# adrone_v1.net
KiCad netlist of a schematic drawn in EAGLE
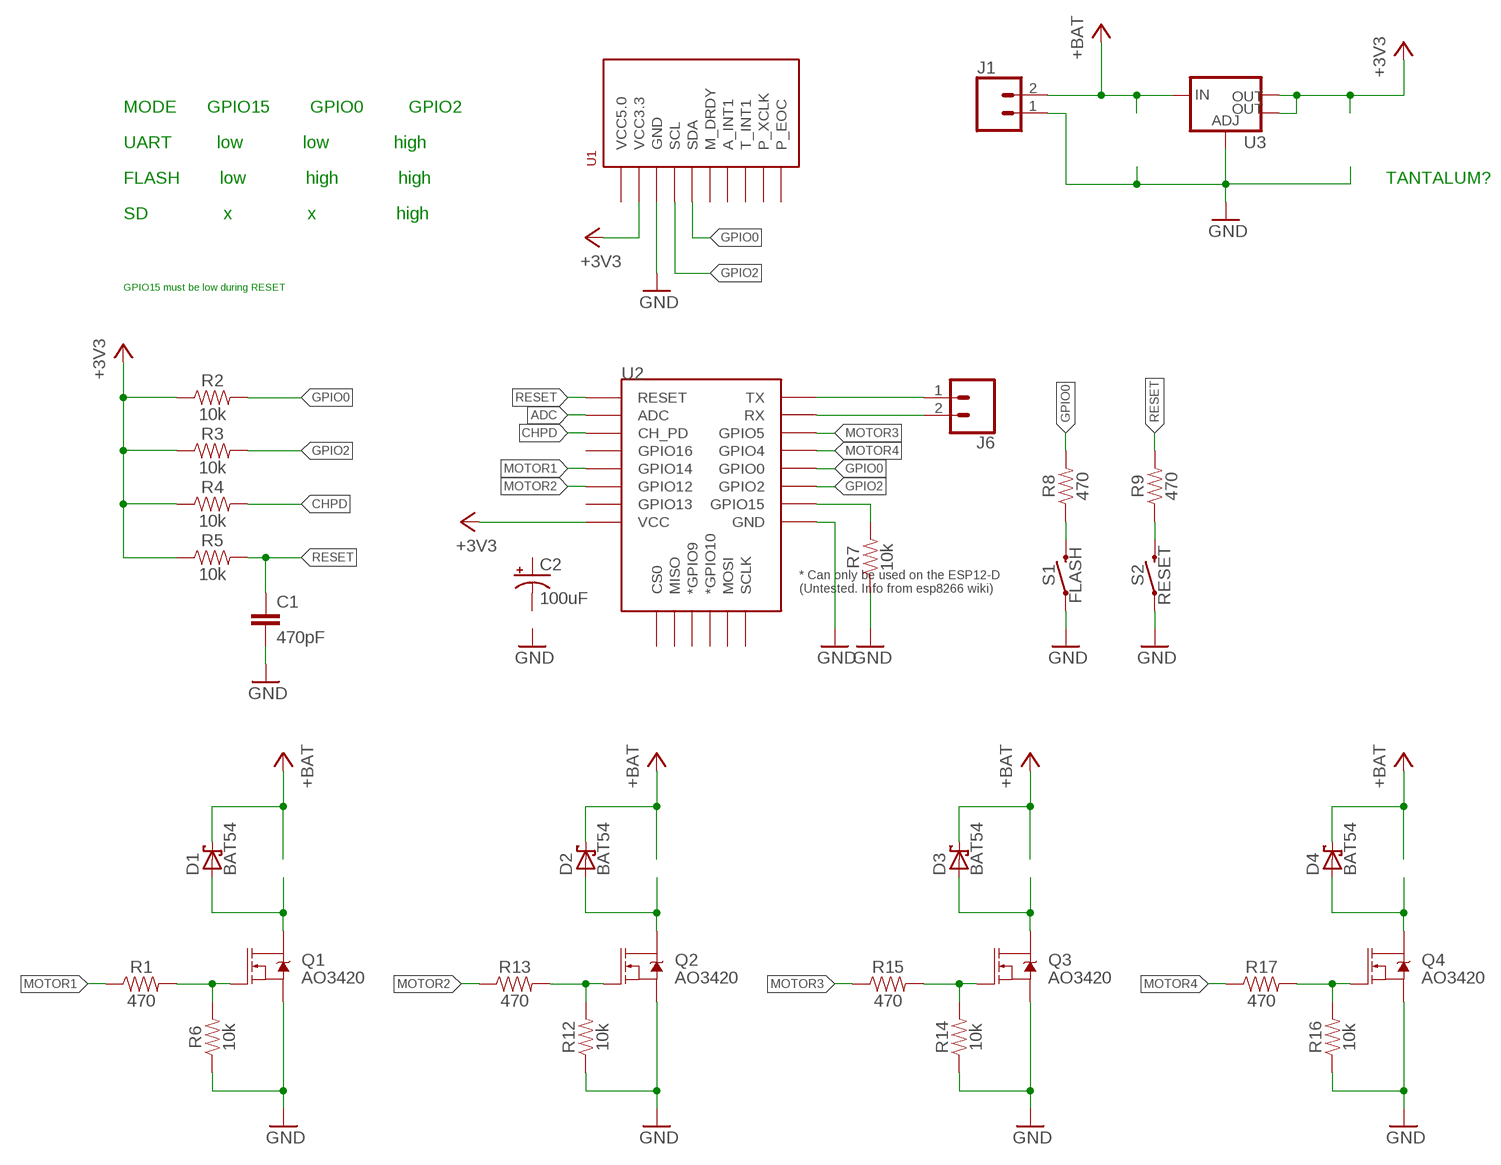
[diagram p0: schematic, sheet 1]

(export (version "E")
  (design (tool "Eeschema 10.0.6"))
  (components
    (comp (ref "C1")
      (value "470pF")
      (footprint "eagle-import:0603")
      (libsource (lib "eagle-import") (part "10NF-0603-50V-10%"))
    )
    (comp (ref "C2")
      (value "100uF")
      (footprint "eagle-import:EIA7343")
      (libsource (lib "eagle-import") (part "100UF-POLAR-EIA7343-10V-10%(TANT)"))
    )
    (comp (ref "D1")
      (value "BAT54")
      (footprint "eagle-import:SOT23")
      (libsource (lib "eagle-import") (part "BAT54"))
    )
    (comp (ref "D2")
      (value "BAT54")
      (footprint "eagle-import:SOT23")
      (libsource (lib "eagle-import") (part "BAT54"))
    )
    (comp (ref "D3")
      (value "BAT54")
      (footprint "eagle-import:SOT23")
      (libsource (lib "eagle-import") (part "BAT54"))
    )
    (comp (ref "D4")
      (value "BAT54")
      (footprint "eagle-import:SOT23")
      (libsource (lib "eagle-import") (part "BAT54"))
    )
    (comp (ref "J1")
      (value "CONN_02")
      (footprint "eagle-import:1X02")
      (libsource (lib "eagle-import") (part "CONN_02"))
    )
    (comp (ref "J6")
      (value "CONN_02")
      (footprint "eagle-import:1X02")
      (libsource (lib "eagle-import") (part "CONN_02"))
    )
    (comp (ref "Q1")
      (value "AO3420")
      (footprint "eagle-import:SOT23-3")
      (libsource (lib "eagle-import") (part "MOSFET-NCH-AO3404A"))
    )
    (comp (ref "Q2")
      (value "AO3420")
      (footprint "eagle-import:SOT23-3")
      (libsource (lib "eagle-import") (part "MOSFET-NCH-AO3404A"))
    )
    (comp (ref "Q3")
      (value "AO3420")
      (footprint "eagle-import:SOT23-3")
      (libsource (lib "eagle-import") (part "MOSFET-NCH-AO3404A"))
    )
    (comp (ref "Q4")
      (value "AO3420")
      (footprint "eagle-import:SOT23-3")
      (libsource (lib "eagle-import") (part "MOSFET-NCH-AO3404A"))
    )
    (comp (ref "R1")
      (value "470")
      (footprint "eagle-import:0603")
      (libsource (lib "eagle-import") (part "10KOHM-0603-1/10W-1%"))
    )
    (comp (ref "R2")
      (value "10k")
      (footprint "eagle-import:0603")
      (libsource (lib "eagle-import") (part "10KOHM-0603-1/10W-1%"))
    )
    (comp (ref "R3")
      (value "10k")
      (footprint "eagle-import:0603")
      (libsource (lib "eagle-import") (part "10KOHM-0603-1/10W-1%"))
    )
    (comp (ref "R4")
      (value "10k")
      (footprint "eagle-import:0603")
      (libsource (lib "eagle-import") (part "10KOHM-0603-1/10W-1%"))
    )
    (comp (ref "R5")
      (value "10k")
      (footprint "eagle-import:0603")
      (libsource (lib "eagle-import") (part "10KOHM-0603-1/10W-1%"))
    )
    (comp (ref "R6")
      (value "10k")
      (footprint "eagle-import:0603")
      (libsource (lib "eagle-import") (part "10KOHM-0603-1/10W-1%"))
    )
    (comp (ref "R7")
      (value "10k")
      (footprint "eagle-import:0603")
      (libsource (lib "eagle-import") (part "10KOHM-0603-1/10W-1%"))
    )
    (comp (ref "R8")
      (value "470")
      (footprint "eagle-import:0603")
      (libsource (lib "eagle-import") (part "470OHM-0603-1/10W-1%"))
    )
    (comp (ref "R9")
      (value "470")
      (footprint "eagle-import:0603")
      (libsource (lib "eagle-import") (part "470OHM-0603-1/10W-1%"))
    )
    (comp (ref "R12")
      (value "10k")
      (footprint "eagle-import:0603")
      (libsource (lib "eagle-import") (part "10KOHM-0603-1/10W-1%"))
    )
    (comp (ref "R13")
      (value "470")
      (footprint "eagle-import:0603")
      (libsource (lib "eagle-import") (part "10KOHM-0603-1/10W-1%"))
    )
    (comp (ref "R14")
      (value "10k")
      (footprint "eagle-import:0603")
      (libsource (lib "eagle-import") (part "10KOHM-0603-1/10W-1%"))
    )
    (comp (ref "R15")
      (value "470")
      (footprint "eagle-import:0603")
      (libsource (lib "eagle-import") (part "10KOHM-0603-1/10W-1%"))
    )
    (comp (ref "R16")
      (value "10k")
      (footprint "eagle-import:0603")
      (libsource (lib "eagle-import") (part "10KOHM-0603-1/10W-1%"))
    )
    (comp (ref "R17")
      (value "470")
      (footprint "eagle-import:0603")
      (libsource (lib "eagle-import") (part "10KOHM-0603-1/10W-1%"))
    )
    (comp (ref "S1")
      (value "FLASH")
      (footprint "eagle-import:TACTILE_SWITCH_SMD_6.0X3.5MM")
      (libsource (lib "eagle-import") (part "MOMENTARY-SWITCH-SPST-SMD-6.0X3.5MM"))
    )
    (comp (ref "S2")
      (value "RESET")
      (footprint "eagle-import:TACTILE_SWITCH_SMD_6.0X3.5MM")
      (libsource (lib "eagle-import") (part "MOMENTARY-SWITCH-SPST-SMD-6.0X3.5MM"))
    )
    (comp (ref "U1")
      (value "GY-80_10DOF")
      (footprint "eagle-import:GY-80_10DOF")
      (libsource (lib "eagle-import") (part "GY-80_10DOF"))
    )
    (comp (ref "U2")
      (value "ESP12ESMD")
      (footprint "eagle-import:ESP12E-SMD")
      (libsource (lib "eagle-import") (part "ESP12ESMD"))
    )
    (comp (ref "U3")
      (value "V_REG_LM1117SOT223")
      (footprint "eagle-import:SOT223")
      (libsource (lib "eagle-import") (part "V_REG_LM1117SOT223"))
    )
  )
  (nets
    (net (code "1") (name "+3V3") (class "Default")
      (node (ref "R2") (pin "1") (pinfunction "1_1") (pintype "passive"))
      (node (ref "R3") (pin "1") (pinfunction "1_1") (pintype "passive"))
      (node (ref "R4") (pin "1") (pinfunction "1_1") (pintype "passive"))
      (node (ref "R5") (pin "1") (pinfunction "1_1") (pintype "passive"))
      (node (ref "U1") (pin "P$2") (pinfunction "VCC3.3_P$2") (pintype "bidirectional"))
      (node (ref "U2") (pin "VCC") (pinfunction "VCC_VCC") (pintype "bidirectional"))
      (node (ref "U3") (pin "2") (pinfunction "OUT_2") (pintype "output"))
      (node (ref "U3") (pin "4") (pinfunction "OUT_4") (pintype "output"))
    )
    (net (code "2") (name "+BAT") (class "Default")
      (node (ref "D1") (pin "3") (pinfunction "C_3") (pintype "passive"))
      (node (ref "D2") (pin "3") (pinfunction "C_3") (pintype "passive"))
      (node (ref "D3") (pin "3") (pinfunction "C_3") (pintype "passive"))
      (node (ref "D4") (pin "3") (pinfunction "C_3") (pintype "passive"))
      (node (ref "J1") (pin "2") (pinfunction "2_2") (pintype "passive"))
      (node (ref "U3") (pin "3") (pinfunction "IN_3") (pintype "input"))
    )
    (net (code "3") (name "ADC") (class "Default")
      (node (ref "U2") (pin "ADC") (pinfunction "ADC_ADC") (pintype "bidirectional"))
    )
    (net (code "4") (name "CHPD") (class "Default")
      (node (ref "R4") (pin "2") (pinfunction "2_2") (pintype "passive"))
      (node (ref "U2") (pin "CH_PD") (pinfunction "CH_PD_CH_PD") (pintype "bidirectional"))
    )
    (net (code "5") (name "GND") (class "Default")
      (node (ref "C1") (pin "2") (pinfunction "2_2") (pintype "passive"))
      (node (ref "J1") (pin "1") (pinfunction "1_1") (pintype "passive"))
      (node (ref "Q1") (pin "2") (pinfunction "S_2") (pintype "bidirectional"))
      (node (ref "Q2") (pin "2") (pinfunction "S_2") (pintype "bidirectional"))
      (node (ref "Q3") (pin "2") (pinfunction "S_2") (pintype "bidirectional"))
      (node (ref "Q4") (pin "2") (pinfunction "S_2") (pintype "bidirectional"))
      (node (ref "R12") (pin "1") (pinfunction "1_1") (pintype "passive"))
      (node (ref "R14") (pin "1") (pinfunction "1_1") (pintype "passive"))
      (node (ref "R16") (pin "1") (pinfunction "1_1") (pintype "passive"))
      (node (ref "R6") (pin "1") (pinfunction "1_1") (pintype "passive"))
      (node (ref "R7") (pin "1") (pinfunction "1_1") (pintype "passive"))
      (node (ref "S1") (pin "1") (pinfunction "1_1") (pintype "passive"))
      (node (ref "S2") (pin "1") (pinfunction "1_1") (pintype "passive"))
      (node (ref "U1") (pin "P$3") (pinfunction "GND_P$3") (pintype "bidirectional"))
      (node (ref "U2") (pin "GND") (pinfunction "GND_GND") (pintype "bidirectional"))
      (node (ref "U3") (pin "1") (pinfunction "ADJ_1") (pintype "input"))
    )
    (net (code "6") (name "GPIO0") (class "Default")
      (node (ref "R2") (pin "2") (pinfunction "2_2") (pintype "passive"))
      (node (ref "R8") (pin "2") (pinfunction "2_2") (pintype "passive"))
      (node (ref "U1") (pin "P$5") (pinfunction "SDA_P$5") (pintype "bidirectional"))
      (node (ref "U2") (pin "GPIO0") (pinfunction "GPIO0_GPIO0") (pintype "bidirectional"))
    )
    (net (code "7") (name "GPIO2") (class "Default")
      (node (ref "R3") (pin "2") (pinfunction "2_2") (pintype "passive"))
      (node (ref "U1") (pin "P$4") (pinfunction "SCL_P$4") (pintype "bidirectional"))
      (node (ref "U2") (pin "GPIO2") (pinfunction "GPIO2_GPIO2") (pintype "bidirectional"))
    )
    (net (code "8") (name "MOTOR1") (class "Default")
      (node (ref "R1") (pin "1") (pinfunction "1_1") (pintype "passive"))
      (node (ref "U2") (pin "GPIO14") (pinfunction "GPIO14_GPIO14") (pintype "bidirectional"))
    )
    (net (code "9") (name "MOTOR2") (class "Default")
      (node (ref "R13") (pin "1") (pinfunction "1_1") (pintype "passive"))
      (node (ref "U2") (pin "GPIO12") (pinfunction "GPIO12_GPIO12") (pintype "bidirectional"))
    )
    (net (code "10") (name "MOTOR3") (class "Default")
      (node (ref "R15") (pin "1") (pinfunction "1_1") (pintype "passive"))
      (node (ref "U2") (pin "GPIO5") (pinfunction "GPIO5_GPIO5") (pintype "bidirectional"))
    )
    (net (code "11") (name "MOTOR4") (class "Default")
      (node (ref "R17") (pin "1") (pinfunction "1_1") (pintype "passive"))
      (node (ref "U2") (pin "GPIO4") (pinfunction "GPIO4_GPIO4") (pintype "bidirectional"))
    )
    (net (code "12") (name "Net-(D1-A)") (class "Default")
      (node (ref "D1") (pin "1") (pinfunction "A_1") (pintype "passive"))
      (node (ref "Q1") (pin "3") (pinfunction "D_3") (pintype "bidirectional"))
    )
    (net (code "13") (name "Net-(D2-A)") (class "Default")
      (node (ref "D2") (pin "1") (pinfunction "A_1") (pintype "passive"))
      (node (ref "Q2") (pin "3") (pinfunction "D_3") (pintype "bidirectional"))
    )
    (net (code "14") (name "Net-(D3-A)") (class "Default")
      (node (ref "D3") (pin "1") (pinfunction "A_1") (pintype "passive"))
      (node (ref "Q3") (pin "3") (pinfunction "D_3") (pintype "bidirectional"))
    )
    (net (code "15") (name "Net-(D4-A)") (class "Default")
      (node (ref "D4") (pin "1") (pinfunction "A_1") (pintype "passive"))
      (node (ref "Q4") (pin "3") (pinfunction "D_3") (pintype "bidirectional"))
    )
    (net (code "16") (name "Net-(Q1-G)") (class "Default")
      (node (ref "Q1") (pin "1") (pinfunction "G_1") (pintype "bidirectional"))
      (node (ref "R1") (pin "2") (pinfunction "2_2") (pintype "passive"))
      (node (ref "R6") (pin "2") (pinfunction "2_2") (pintype "passive"))
    )
    (net (code "17") (name "Net-(Q2-G)") (class "Default")
      (node (ref "Q2") (pin "1") (pinfunction "G_1") (pintype "bidirectional"))
      (node (ref "R12") (pin "2") (pinfunction "2_2") (pintype "passive"))
      (node (ref "R13") (pin "2") (pinfunction "2_2") (pintype "passive"))
    )
    (net (code "18") (name "Net-(Q3-G)") (class "Default")
      (node (ref "Q3") (pin "1") (pinfunction "G_1") (pintype "bidirectional"))
      (node (ref "R14") (pin "2") (pinfunction "2_2") (pintype "passive"))
      (node (ref "R15") (pin "2") (pinfunction "2_2") (pintype "passive"))
    )
    (net (code "19") (name "Net-(Q4-G)") (class "Default")
      (node (ref "Q4") (pin "1") (pinfunction "G_1") (pintype "bidirectional"))
      (node (ref "R16") (pin "2") (pinfunction "2_2") (pintype "passive"))
      (node (ref "R17") (pin "2") (pinfunction "2_2") (pintype "passive"))
    )
    (net (code "20") (name "Net-(R7-Pad2)") (class "Default")
      (node (ref "R7") (pin "2") (pinfunction "2_2") (pintype "passive"))
      (node (ref "U2") (pin "GPIO15") (pinfunction "GPIO15_GPIO15") (pintype "bidirectional"))
    )
    (net (code "21") (name "Net-(R8-Pad1)") (class "Default")
      (node (ref "R8") (pin "1") (pinfunction "1_1") (pintype "passive"))
      (node (ref "S1") (pin "2") (pinfunction "2_2") (pintype "passive"))
    )
    (net (code "22") (name "Net-(R9-Pad1)") (class "Default")
      (node (ref "R9") (pin "1") (pinfunction "1_1") (pintype "passive"))
      (node (ref "S2") (pin "2") (pinfunction "2_2") (pintype "passive"))
    )
    (net (code "23") (name "Net-(U2-RX)") (class "Default")
      (node (ref "J6") (pin "2") (pinfunction "2_2") (pintype "passive"))
      (node (ref "U2") (pin "RXD0") (pinfunction "RX_RXD0") (pintype "bidirectional"))
    )
    (net (code "24") (name "Net-(U2-TX)") (class "Default")
      (node (ref "J6") (pin "1") (pinfunction "1_1") (pintype "passive"))
      (node (ref "U2") (pin "TXD0") (pinfunction "TX_TXD0") (pintype "bidirectional"))
    )
    (net (code "25") (name "RESET") (class "Default")
      (node (ref "C1") (pin "1") (pinfunction "1_1") (pintype "passive"))
      (node (ref "R5") (pin "2") (pinfunction "2_2") (pintype "passive"))
      (node (ref "R9") (pin "2") (pinfunction "2_2") (pintype "passive"))
      (node (ref "U2") (pin "RESET") (pinfunction "RESET_RESET") (pintype "bidirectional"))
    )
    (net (code "26") (name "unconnected-(C2-+-PadA)") (class "Default")
      (node (ref "C2") (pin "A") (pinfunction "+_A") (pintype "passive"))
    )
    (net (code "27") (name "unconnected-(C2---PadC)") (class "Default")
      (node (ref "C2") (pin "C") (pinfunction "-_C") (pintype "passive"))
    )
    (net (code "28") (name "unconnected-(U1-A_INT1-PadP$7)") (class "Default")
      (node (ref "U1") (pin "P$7") (pinfunction "A_INT1_P$7") (pintype "bidirectional"))
    )
    (net (code "29") (name "unconnected-(U1-M_DRDY-PadP$6)") (class "Default")
      (node (ref "U1") (pin "P$6") (pinfunction "M_DRDY_P$6") (pintype "bidirectional"))
    )
    (net (code "30") (name "unconnected-(U1-P_EOC-PadP$10)") (class "Default")
      (node (ref "U1") (pin "P$10") (pinfunction "P_EOC_P$10") (pintype "bidirectional"))
    )
    (net (code "31") (name "unconnected-(U1-P_XCLK-PadP$9)") (class "Default")
      (node (ref "U1") (pin "P$9") (pinfunction "P_XCLK_P$9") (pintype "bidirectional"))
    )
    (net (code "32") (name "unconnected-(U1-T_INT1-PadP$8)") (class "Default")
      (node (ref "U1") (pin "P$8") (pinfunction "T_INT1_P$8") (pintype "bidirectional"))
    )
    (net (code "33") (name "unconnected-(U1-VCC5.0-PadP$1)") (class "Default")
      (node (ref "U1") (pin "P$1") (pinfunction "VCC5.0_P$1") (pintype "bidirectional"))
    )
    (net (code "34") (name "unconnected-(U2-*GPIO9-PadGPIO9)") (class "Default")
      (node (ref "U2") (pin "GPIO9") (pinfunction "*GPIO9_GPIO9") (pintype "bidirectional"))
    )
    (net (code "35") (name "unconnected-(U2-*GPIO10-PadGPIO10)") (class "Default")
      (node (ref "U2") (pin "GPIO10") (pinfunction "*GPIO10_GPIO10") (pintype "bidirectional"))
    )
    (net (code "36") (name "unconnected-(U2-PadCS0)") (class "Default")
      (node (ref "U2") (pin "CS0") (pinfunction "CS0_CS0") (pintype "bidirectional"))
    )
    (net (code "37") (name "unconnected-(U2-PadGPIO13)") (class "Default")
      (node (ref "U2") (pin "GPIO13") (pinfunction "GPIO13_GPIO13") (pintype "bidirectional"))
    )
    (net (code "38") (name "unconnected-(U2-PadGPIO16)") (class "Default")
      (node (ref "U2") (pin "GPIO16") (pinfunction "GPIO16_GPIO16") (pintype "bidirectional"))
    )
    (net (code "39") (name "unconnected-(U2-PadMISO)") (class "Default")
      (node (ref "U2") (pin "MISO") (pinfunction "MISO_MISO") (pintype "bidirectional"))
    )
    (net (code "40") (name "unconnected-(U2-PadMOSI)") (class "Default")
      (node (ref "U2") (pin "MOSI") (pinfunction "MOSI_MOSI") (pintype "bidirectional"))
    )
    (net (code "41") (name "unconnected-(U2-PadSCLK)") (class "Default")
      (node (ref "U2") (pin "SCLK") (pinfunction "SCLK_SCLK") (pintype "bidirectional"))
    )
  )
)
